# EducationalBoardV2F103RBT6.net
KiCad netlist of a schematic drawn in Altium Designer
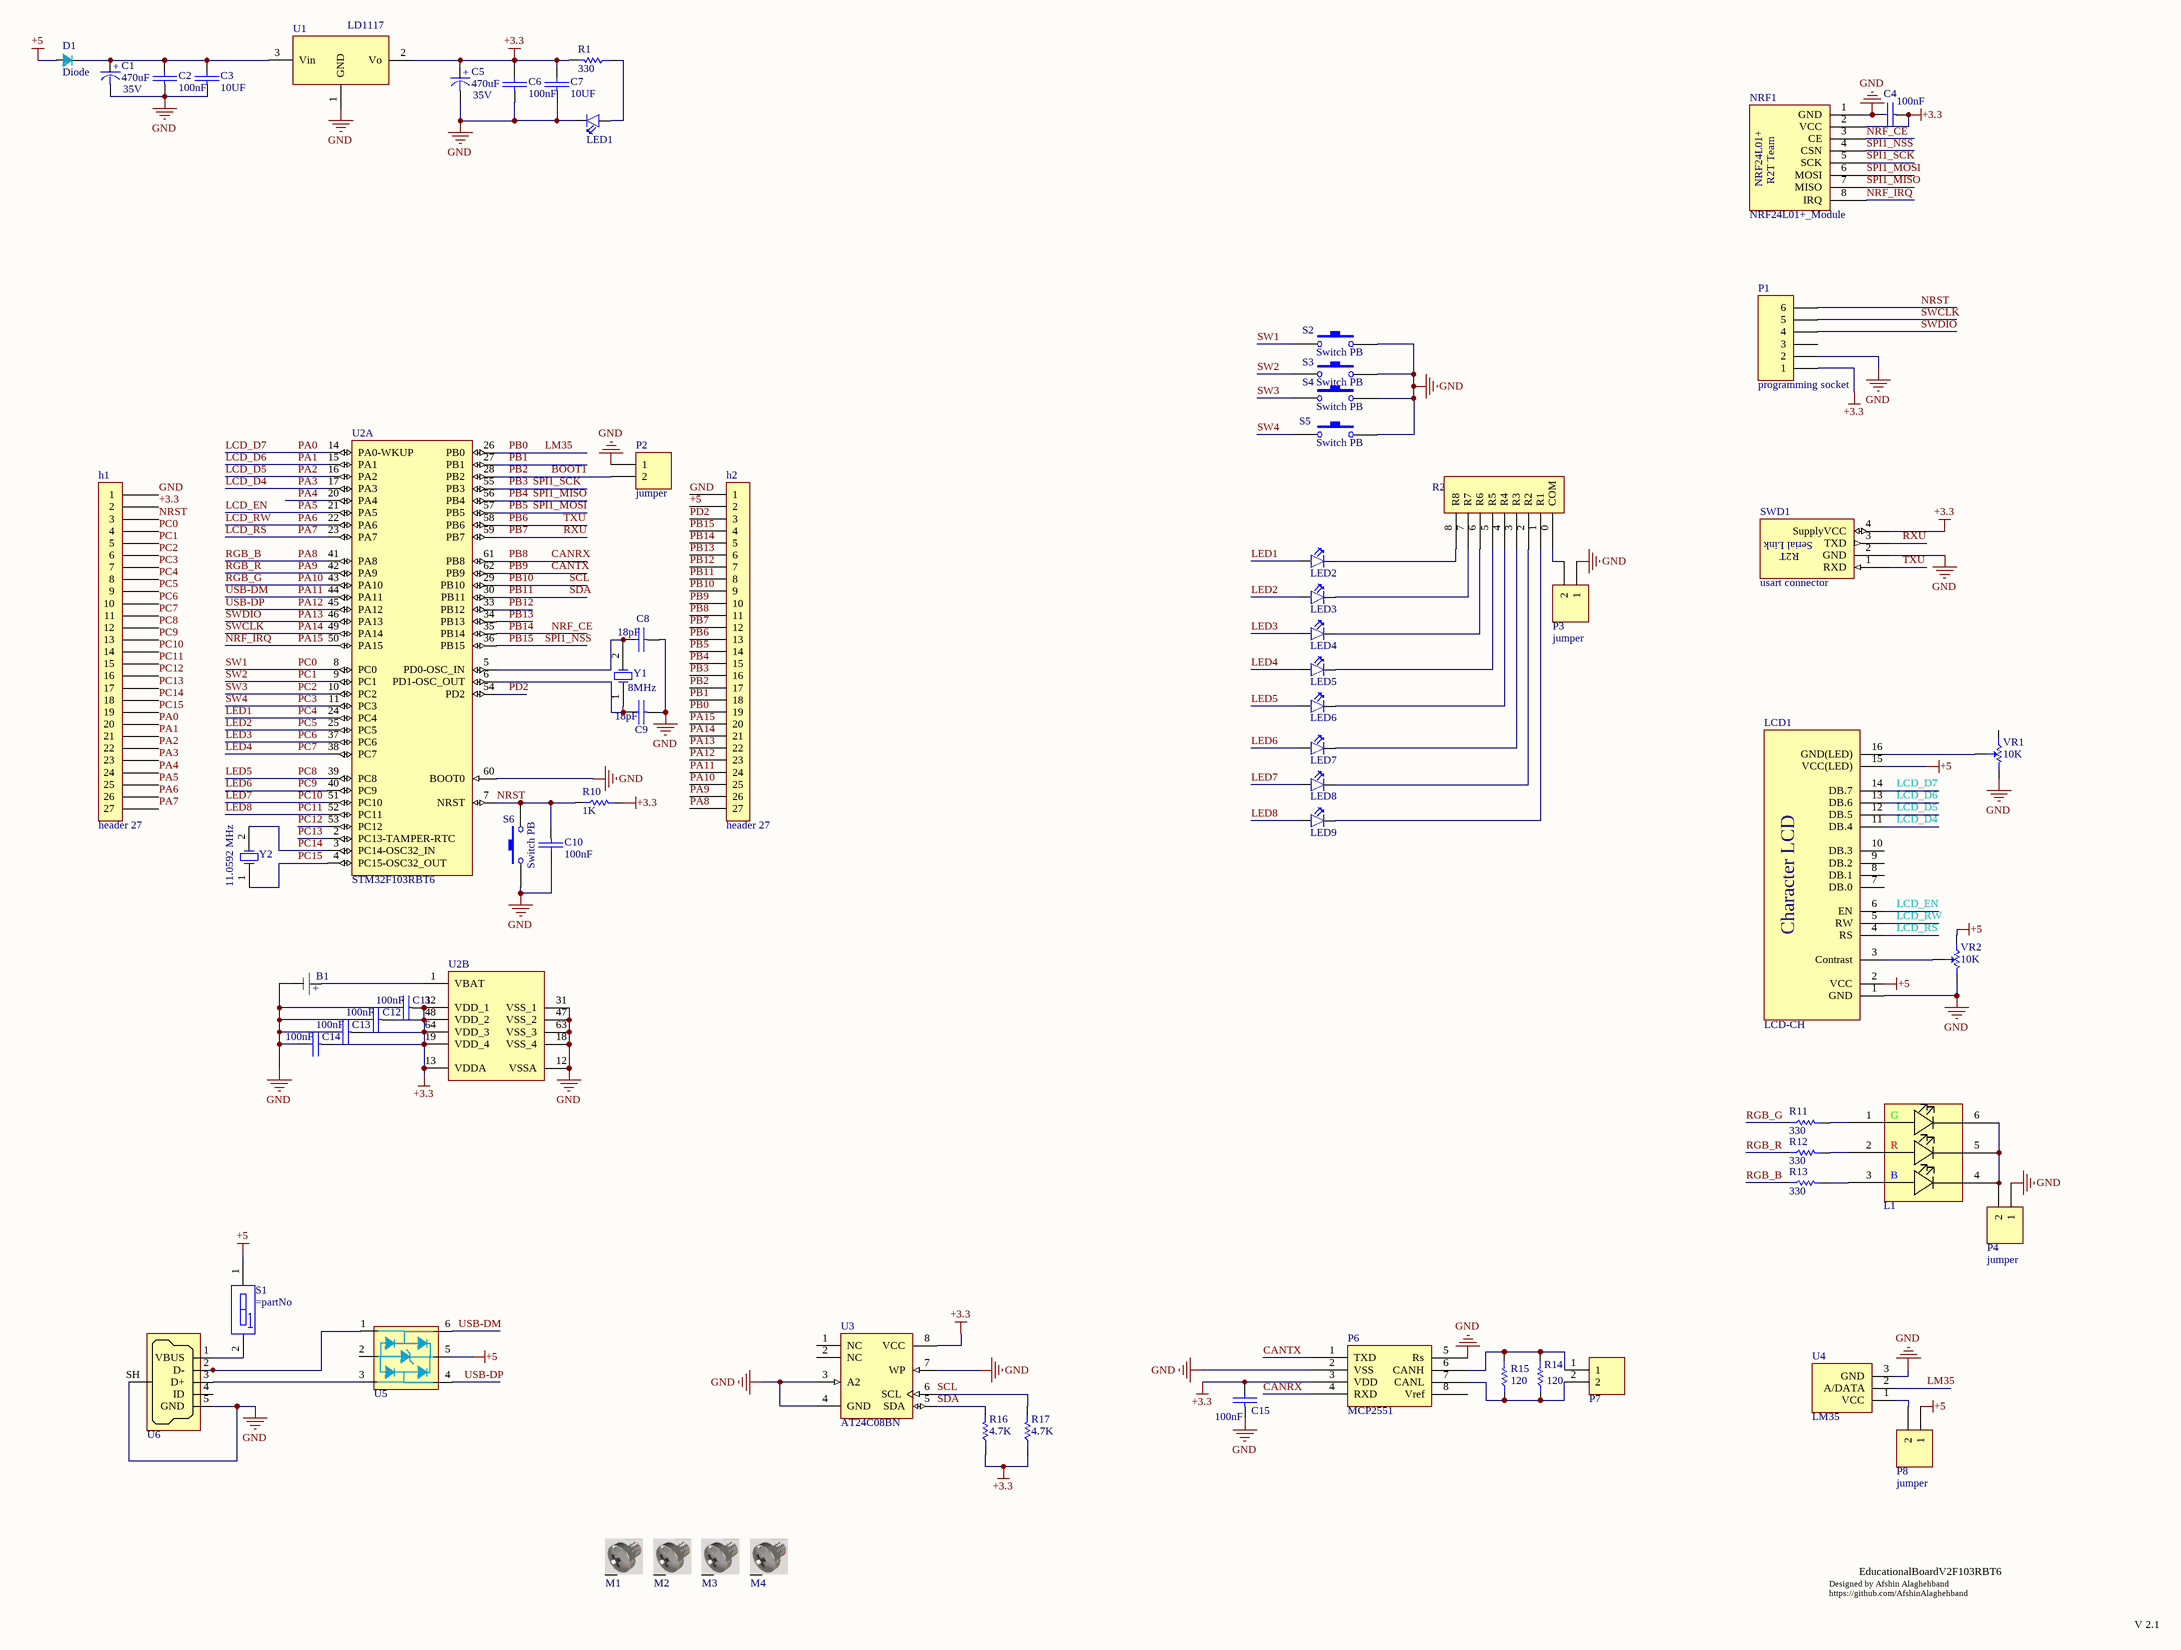
[diagram p0: EducationalBoardV2F103RBT6.SchDoc]

(export (version "E")
  (design (tool "Eeschema 10.0.6"))
  (components
    (comp (ref "B1")
      (value "BatteryHolder")
      (footprint "Battery Holder CR1220-SMD")
      (libsource (lib "R2T Team Library") (part "BatteryHolder"))
    )
    (comp (ref "C1")
      (value "470uF")
      (footprint "cap 03")
      (description "Polar Capacitor")
      (fields (field (name "VOLTAGE") "35V") (field (name "DESIGNER") "Saeid Jorablo"))
      (libsource (lib "My Library") (part "Cap-Polar"))
    )
    (comp (ref "C2")
      (value "100nF")
      (footprint "SMD_CAP_0805")
      (description "Bipolar Capacitor")
      (fields (field (name "VOLTAGE") "100V") (field (name "DESIGNER") "Saeid Jorablo"))
      (libsource (lib "My Library") (part "Cap-Bipolar"))
    )
    (comp (ref "C3")
      (value "10UF")
      (footprint "SMD_CAP_0805")
      (description "Bipolar Capacitor")
      (fields (field (name "VOLTAGE") "100V") (field (name "DESIGNER") "Saeid Jorablo"))
      (libsource (lib "My Library") (part "Cap-Bipolar"))
    )
    (comp (ref "C4")
      (value "100nF")
      (footprint "SMD_CAP_0805")
      (description "Bipolar Capacitor")
      (fields (field (name "VOLTAGE") "100V") (field (name "DESIGNER") "Saeid Jorablo"))
      (libsource (lib "My Library") (part "Cap-Bipolar"))
    )
    (comp (ref "C5")
      (value "470uF")
      (footprint "cap 03")
      (description "Polar Capacitor")
      (fields (field (name "VOLTAGE") "35V") (field (name "DESIGNER") "Saeid Jorablo"))
      (libsource (lib "My Library") (part "Cap-Polar"))
    )
    (comp (ref "C6")
      (value "100nF")
      (footprint "SMD_CAP_0805")
      (description "Bipolar Capacitor")
      (fields (field (name "VOLTAGE") "100V") (field (name "DESIGNER") "Saeid Jorablo"))
      (libsource (lib "My Library") (part "Cap-Bipolar"))
    )
    (comp (ref "C7")
      (value "10UF")
      (footprint "SMD_CAP_0805")
      (description "Bipolar Capacitor")
      (fields (field (name "VOLTAGE") "100V") (field (name "DESIGNER") "Saeid Jorablo"))
      (libsource (lib "My Library") (part "Cap-Bipolar"))
    )
    (comp (ref "C8")
      (value "18pF")
      (footprint "SMD_CAP_1206")
      (description "Bipolar Capacitor")
      (fields (field (name "VOLTAGE") "100V") (field (name "DESIGNER") "Saeid Jorablo"))
      (libsource (lib "My Library") (part "Cap-Bipolar"))
    )
    (comp (ref "C9")
      (value "18pF")
      (footprint "SMD_CAP_1206")
      (description "Bipolar Capacitor")
      (fields (field (name "VOLTAGE") "100V") (field (name "DESIGNER") "Saeid Jorablo"))
      (libsource (lib "My Library") (part "Cap-Bipolar"))
    )
    (comp (ref "C10")
      (value "100nF")
      (footprint "SMD_CAP_0805")
      (description "Bipolar Capacitor")
      (fields (field (name "VOLTAGE") "100V") (field (name "DESIGNER") "Saeid Jorablo"))
      (libsource (lib "My Library") (part "Cap-Bipolar"))
    )
    (comp (ref "C11")
      (value "100nF")
      (footprint "SMD_CAP_0805")
      (description "Bipolar Capacitor")
      (fields (field (name "VOLTAGE") "100V") (field (name "DESIGNER") "Saeid Jorablo"))
      (libsource (lib "My Library") (part "Cap-Bipolar"))
    )
    (comp (ref "C12")
      (value "100nF")
      (footprint "SMD_CAP_0805")
      (description "Bipolar Capacitor")
      (fields (field (name "VOLTAGE") "100V") (field (name "DESIGNER") "Saeid Jorablo"))
      (libsource (lib "My Library") (part "Cap-Bipolar"))
    )
    (comp (ref "C13")
      (value "100nF")
      (footprint "SMD_CAP_0805")
      (description "Bipolar Capacitor")
      (fields (field (name "VOLTAGE") "100V") (field (name "DESIGNER") "Saeid Jorablo"))
      (libsource (lib "My Library") (part "Cap-Bipolar"))
    )
    (comp (ref "C14")
      (value "100nF")
      (footprint "SMD_CAP_0805")
      (description "Bipolar Capacitor")
      (fields (field (name "VOLTAGE") "100V") (field (name "DESIGNER") "Saeid Jorablo"))
      (libsource (lib "My Library") (part "Cap-Bipolar"))
    )
    (comp (ref "C15")
      (value "100nF")
      (footprint "SMD_CAP_0805")
      (description "Bipolar Capacitor")
      (fields (field (name "VOLTAGE") "100V") (field (name "DESIGNER") "Saeid Jorablo"))
      (libsource (lib "My Library") (part "Cap-Bipolar"))
    )
    (comp (ref "D1")
      (value "Diodes")
      (footprint "DO-214AC ( SMD Diode )")
      (fields (field (name "DESCRIPTION:") "Diode") (field (name "DESIGNER :") "Hamed Jafarzadeh"))
      (libsource (lib "R2T Team Library") (part "Diodes"))
    )
    (comp (ref "h1")
      (value "header 27")
      (footprint "PCBComponent_1")
      (libsource (lib "my_lib_header27") (part "header 27"))
    )
    (comp (ref "h2")
      (value "header 27")
      (footprint "PCBComponent_1")
      (libsource (lib "") (part "header 27_1"))
    )
    (comp (ref "L1")
      (value "LED RGB")
      (footprint "LED_5050")
      (description "LED 5050 RGB")
      (libsource (lib "My_Lib_LED_RGB_5050") (part "LED RGB"))
    )
    (comp (ref "LCD1") (value "LCD-CH") (footprint "LCD2-16") (libsource (lib "My_lib_new") (part "LCD-CH")))
    (comp (ref "LED1")
      (value "LED")
      (footprint "LED0805")
      (fields (field (name "DESIGNER :") "Razi Research Team Of Mashhad - Hamed Jafarzadeh"))
      (libsource (lib "R2T Team Library") (part "LED"))
    )
    (comp (ref "LED2")
      (value "LED")
      (footprint "LED0805")
      (description "LED Red")
      (fields (field (name "DESIGNER :") "Razi Research Team Of Mashhad - Hamed Jafarzadeh"))
      (libsource (lib "R2T Team Library") (part "LED"))
    )
    (comp (ref "LED3")
      (value "LED")
      (footprint "LED0805")
      (description "LED Red")
      (fields (field (name "DESIGNER :") "Razi Research Team Of Mashhad - Hamed Jafarzadeh"))
      (libsource (lib "R2T Team Library") (part "LED"))
    )
    (comp (ref "LED4")
      (value "LED")
      (footprint "LED0805")
      (description "LED Red")
      (fields (field (name "DESIGNER :") "Razi Research Team Of Mashhad - Hamed Jafarzadeh"))
      (libsource (lib "R2T Team Library") (part "LED"))
    )
    (comp (ref "LED5")
      (value "LED")
      (footprint "LED0805")
      (description "LED Red")
      (fields (field (name "DESIGNER :") "Razi Research Team Of Mashhad - Hamed Jafarzadeh"))
      (libsource (lib "R2T Team Library") (part "LED"))
    )
    (comp (ref "LED6")
      (value "LED")
      (footprint "LED0805")
      (description "LED Red")
      (fields (field (name "DESIGNER :") "Razi Research Team Of Mashhad - Hamed Jafarzadeh"))
      (libsource (lib "R2T Team Library") (part "LED"))
    )
    (comp (ref "LED7")
      (value "LED")
      (footprint "LED0805")
      (description "LED Red")
      (fields (field (name "DESIGNER :") "Razi Research Team Of Mashhad - Hamed Jafarzadeh"))
      (libsource (lib "R2T Team Library") (part "LED"))
    )
    (comp (ref "LED8")
      (value "LED")
      (footprint "LED0805")
      (description "LED Red")
      (fields (field (name "DESIGNER :") "Razi Research Team Of Mashhad - Hamed Jafarzadeh"))
      (libsource (lib "R2T Team Library") (part "LED"))
    )
    (comp (ref "LED9")
      (value "LED")
      (footprint "LED0805")
      (description "LED Red")
      (fields (field (name "DESIGNER :") "Razi Research Team Of Mashhad - Hamed Jafarzadeh"))
      (libsource (lib "R2T Team Library") (part "LED"))
    )
    (comp (ref "M1")
      (value "Screw")
      (footprint "Board Screw_No Silk")
      (description "Board Screw With Spacer")
      (libsource (lib "My Library") (part "Board Screw"))
    )
    (comp (ref "M2")
      (value "Screw")
      (footprint "Board Screw_No Silk")
      (description "Board Screw With Spacer")
      (libsource (lib "My Library") (part "Board Screw"))
    )
    (comp (ref "M3")
      (value "Screw")
      (footprint "Board Screw_No Silk")
      (description "Board Screw With Spacer")
      (libsource (lib "My Library") (part "Board Screw"))
    )
    (comp (ref "M4")
      (value "Screw")
      (footprint "Board Screw_No Silk")
      (description "Board Screw With Spacer")
      (libsource (lib "My Library") (part "Board Screw"))
    )
    (comp (ref "NRF1")
      (value "NRF24L01+_Module")
      (footprint "NRF24L01+_Module")
      (fields (field (name "DESIGNER:") "HamedJafarzadeh"))
      (libsource (lib "R2T Team Library") (part "NRF24L01+_Module"))
    )
    (comp (ref "P1")
      (value "programming socket")
      (footprint "HDR1X6")
      (description "Header, 6-Pin")
      (fields (field (name "PUBLISHER") "Altium Limited"))
      (libsource (lib "Miscellaneous Connectors") (part "Header 6"))
    )
    (comp (ref "P2")
      (value "jumper")
      (footprint "HDR1X2")
      (description "Header, 2-Pin")
      (fields (field (name "PUBLISHER") "Altium Limited"))
      (libsource (lib "") (part "Header 2_1"))
    )
    (comp (ref "P3")
      (value "jumper")
      (footprint "HDR1X2")
      (description "Header, 2-Pin")
      (fields (field (name "PUBLISHER") "Altium Limited"))
      (libsource (lib "Miscellaneous Connectors") (part "Header 2"))
    )
    (comp (ref "P4")
      (value "jumper")
      (footprint "HDR1X2")
      (description "Header, 2-Pin")
      (fields (field (name "PUBLISHER") "Altium Limited"))
      (libsource (lib "Miscellaneous Connectors") (part "Header 2"))
    )
    (comp (ref "P6")
      (value "MCP2551")
      (footprint "MCP2551")
      (description "CAN TRANSCEIVERS")
      (libsource (lib "my_lib_MCP2552") (part "MCP2551"))
    )
    (comp (ref "P7")
      (value "can Connector")
      (footprint "PH Connector 2Pin")
      (fields (field (name "DESIGNER:") "Hamed Jafarzadeh - www.R2T.ir"))
      (libsource (lib "R2T Team Library") (part "Connector 2Pin"))
    )
    (comp (ref "P8")
      (value "jumper")
      (footprint "HDR1X2")
      (description "Header, 2-Pin")
      (fields (field (name "PUBLISHER") "Altium Limited"))
      (libsource (lib "Miscellaneous Connectors") (part "Header 2"))
    )
    (comp (ref "R1")
      (value "330")
      (footprint "RES 0805 (2012X06L)")
      (description "Resistor")
      (fields (field (name "TOLERANCE") "5%") (field (name "POWER") "1/8 W"))
      (libsource (lib "My Library") (part "Resistor"))
    )
    (comp (ref "R2")
      (value "ArrayResistor9pin")
      (footprint "ArrayRes9")
      (libsource (lib "My_Lib_ArrayResistor_9") (part "ArrayResistor9pin"))
    )
    (comp (ref "R10")
      (value "1K")
      (footprint "RES 0805 (2012X06L)")
      (description "Resistor")
      (fields (field (name "TOLERANCE") "5%") (field (name "POWER") "1/8 W"))
      (libsource (lib "My Library") (part "Resistor"))
    )
    (comp (ref "R11")
      (value "330")
      (footprint "RES 0805 (2012X06L)")
      (description "Resistor")
      (fields (field (name "TOLERANCE") "5%") (field (name "POWER") "1/8 W"))
      (libsource (lib "My Library") (part "Resistor"))
    )
    (comp (ref "R12")
      (value "330")
      (footprint "RES 0805 (2012X06L)")
      (description "Resistor")
      (fields (field (name "TOLERANCE") "5%") (field (name "POWER") "1/8 W"))
      (libsource (lib "My Library") (part "Resistor"))
    )
    (comp (ref "R13")
      (value "330")
      (footprint "RES 0805 (2012X06L)")
      (description "Resistor")
      (fields (field (name "TOLERANCE") "5%") (field (name "POWER") "1/8 W"))
      (libsource (lib "My Library") (part "Resistor"))
    )
    (comp (ref "R14")
      (value "120")
      (footprint "RES 0805 (2012X06L)")
      (description "Resistor")
      (libsource (lib "My Library") (part "Resistor"))
    )
    (comp (ref "R15")
      (value "120")
      (footprint "RES 0805 (2012X06L)")
      (description "Resistor")
      (fields (field (name "TOLERANCE") "5%") (field (name "POWER") "1/8 W"))
      (libsource (lib "My Library") (part "Resistor"))
    )
    (comp (ref "R16")
      (value "4.7K")
      (footprint "RES 0805 (2012X06L)")
      (description "Resistor")
      (fields (field (name "TOLERANCE") "5%") (field (name "POWER") "1/8 W"))
      (libsource (lib "My Library") (part "Resistor"))
    )
    (comp (ref "R17")
      (value "4.7K")
      (footprint "RES 0805 (2012X06L)")
      (description "Resistor")
      (fields (field (name "TOLERANCE") "5%") (field (name "POWER") "1/8 W"))
      (libsource (lib "My Library") (part "Resistor"))
    )
    (comp (ref "S1")
      (value "~")
      (footprint "418117170901")
      (description "WS-DITV 2.54 mm compact THT with flat actuator")
      (fields
        (field (name "MANUFACTURER") "Wurth Elektronik")
        (field (name "PART NO.") "418117170901")
        (field (name "CREATED BY") "Baojun Chen")
      )
      (libsource (lib "R2T Team Library") (part "DipSwitch1"))
    )
    (comp (ref "S2")
      (value "Switch PB")
      (footprint "SW-PB")
      (description "Push Button Switch")
      (libsource (lib "My Library") (part "Switch PB"))
    )
    (comp (ref "S3")
      (value "Switch PB")
      (footprint "SW-PB")
      (description "Push Button Switch")
      (libsource (lib "My Library") (part "Switch PB"))
    )
    (comp (ref "S4")
      (value "Switch PB")
      (footprint "SW-PB")
      (description "Push Button Switch")
      (libsource (lib "My Library") (part "Switch PB"))
    )
    (comp (ref "S5")
      (value "Switch PB")
      (footprint "SW-PB")
      (description "Push Button Switch")
      (libsource (lib "My Library") (part "Switch PB"))
    )
    (comp (ref "S6")
      (value "Switch PB")
      (footprint "SW-PB")
      (description "Push Button Switch")
      (libsource (lib "My Library") (part "Switch PB"))
    )
    (comp (ref "SWD1")
      (value "usart connector")
      (footprint "SerialWireMini")
      (libsource (lib "R2T Team Library") (part "R2T-MiniSerial"))
    )
    (comp (ref "U1") (value "LD1117") (footprint "TO-252-reg") (libsource (lib "AM_LIB") (part "LD1117")))
    (comp (ref "U2")
      (value "STM32F103RBT6")
      (footprint "STM-LQFP64_N")
      (description "ARM Cortex-M3 32-bit MCU")
      (fields (field (name "PARTNUMBER") "STM32F103RBT6"))
      (libsource (lib "ST Microelectronics STM32 F1") (part "STM32F103RBT6"))
    )
    (comp (ref "U3")
      (value "AT24C08BN")
      (footprint "8S1_N")
      (description "Serial EEPROM")
      (libsource (lib "Atmel Serial EEPROM") (part "AT24C08BN-SP25-B"))
    )
    (comp (ref "U4") (value "LM35") (footprint "LM35") (libsource (lib "My_lib_new") (part "LM35")))
    (comp (ref "U5")
      (value "USBLC6-2")
      (footprint "USBLC6-2")
      (description "Very low capacitance ESD protection;")
      (fields (field (name "DESIGNER") "Hamed Jafarzadeh"))
      (libsource (lib "R2T Team Library") (part "USBLC6-2"))
    )
    (comp (ref "U6")
      (value "USB OTG")
      (footprint "USB_Micro")
      (fields (field (name "DESIGNER:") "Hamed Jafarzadeh"))
      (libsource (lib "R2T Team Library") (part "USB OTG"))
    )
    (comp (ref "VR1")
      (value "10K")
      (footprint "Pot 00")
      (description "Variable Resistor")
      (fields (field (name "DESIGNER") "Saeid Jorablo"))
      (libsource (lib "My Library") (part "Resistor Variable"))
    )
    (comp (ref "VR2")
      (value "10K")
      (footprint "Pot 00")
      (description "Variable Resistor")
      (fields (field (name "DESIGNER") "Saeid Jorablo"))
      (libsource (lib "My Library") (part "Resistor Variable"))
    )
    (comp (ref "Y1")
      (value "8MHz")
      (footprint "XTAL Small")
      (description "XTAL Crystal")
      (libsource (lib "My Library") (part "XTAL"))
    )
    (comp (ref "Y2")
      (value "11.0592 MHz")
      (footprint "XTAL RTC")
      (description "XTAL Crystal")
      (libsource (lib "My Library") (part "XTAL"))
    )
  )
  (nets
    (net (code "1") (name "+3.3") (class "Default")
      (node (ref "C11") (pin "2") (pinfunction "-_2") (pintype "passive"))
      (node (ref "C12") (pin "2") (pinfunction "-_2") (pintype "passive"))
      (node (ref "C13") (pin "2") (pinfunction "-_2") (pintype "passive"))
      (node (ref "C14") (pin "2") (pinfunction "-_2") (pintype "passive"))
      (node (ref "C15") (pin "1") (pinfunction "+_1") (pintype "passive"))
      (node (ref "C4") (pin "2") (pinfunction "-_2") (pintype "passive"))
      (node (ref "C5") (pin "1") (pinfunction "+_1") (pintype "passive"))
      (node (ref "C6") (pin "1") (pinfunction "+_1") (pintype "passive"))
      (node (ref "C7") (pin "1") (pinfunction "+_1") (pintype "passive"))
      (node (ref "NRF1") (pin "2") (pinfunction "VCC_2") (pintype "passive"))
      (node (ref "P1") (pin "1") (pinfunction "1_1") (pintype "passive"))
      (node (ref "P6") (pin "3") (pinfunction "VDD_3") (pintype "passive"))
      (node (ref "R1") (pin "2") (pinfunction "2_2") (pintype "passive"))
      (node (ref "R10") (pin "2") (pinfunction "2_2") (pintype "passive"))
      (node (ref "R16") (pin "1") (pinfunction "1_1") (pintype "passive"))
      (node (ref "R17") (pin "1") (pinfunction "1_1") (pintype "passive"))
      (node (ref "SWD1") (pin "4") (pinfunction "SupplyVCC_4") (pintype "bidirectional"))
      (node (ref "U1") (pin "2") (pinfunction "Vo_2") (pintype "passive"))
      (node (ref "U2") (pin "13") (pinfunction "VDDA_13") (pintype "power_in"))
      (node (ref "U2") (pin "19") (pinfunction "VDD_4_19") (pintype "power_in"))
      (node (ref "U2") (pin "32") (pinfunction "VDD_1_32") (pintype "power_in"))
      (node (ref "U2") (pin "48") (pinfunction "VDD_2_48") (pintype "power_in"))
      (node (ref "U2") (pin "64") (pinfunction "VDD_3_64") (pintype "power_in"))
      (node (ref "U3") (pin "8") (pinfunction "VCC_8") (pintype "power_in"))
      (node (ref "h1") (pin "2") (pinfunction "2_2") (pintype "passive"))
    )
    (net (code "2") (name "+5") (class "Default")
      (node (ref "D1") (pin "0") (pintype "passive"))
      (node (ref "LCD1") (pin "15") (pinfunction "VCC(LED)_15") (pintype "passive"))
      (node (ref "LCD1") (pin "2") (pinfunction "VCC_2") (pintype "passive"))
      (node (ref "P8") (pin "1") (pinfunction "1_1") (pintype "passive"))
      (node (ref "S1") (pin "1") (pinfunction "1_1") (pintype "passive"))
      (node (ref "U5") (pin "5") (pinfunction "0_5") (pintype "passive"))
      (node (ref "VR2") (pin "1") (pinfunction "CCW_1") (pintype "passive"))
      (node (ref "h2") (pin "2") (pinfunction "2_2") (pintype "passive"))
    )
    (net (code "3") (name "/BOOT1") (class "Default")
      (node (ref "P2") (pin "2") (pinfunction "2_2") (pintype "passive"))
      (node (ref "U2") (pin "28") (pinfunction "PB2_28") (pintype "bidirectional"))
      (node (ref "h2") (pin "17") (pinfunction "17_17") (pintype "passive"))
    )
    (net (code "4") (name "/CANRX") (class "Default")
      (node (ref "P6") (pin "4") (pinfunction "RXD_4") (pintype "passive"))
      (node (ref "U2") (pin "61") (pinfunction "PB8_61") (pintype "bidirectional"))
      (node (ref "h2") (pin "11") (pinfunction "11_11") (pintype "passive"))
    )
    (net (code "5") (name "/CANTX") (class "Default")
      (node (ref "P6") (pin "1") (pinfunction "TXD_1") (pintype "passive"))
      (node (ref "U2") (pin "62") (pinfunction "PB9_62") (pintype "bidirectional"))
      (node (ref "h2") (pin "10") (pinfunction "10_10") (pintype "passive"))
    )
    (net (code "6") (name "/LCD_D4") (class "Default")
      (node (ref "LCD1") (pin "11") (pinfunction "DB.4_11") (pintype "passive"))
      (node (ref "U2") (pin "17") (pinfunction "PA3_17") (pintype "bidirectional"))
      (node (ref "h1") (pin "23") (pinfunction "23_23") (pintype "passive"))
    )
    (net (code "7") (name "/LCD_D5") (class "Default")
      (node (ref "LCD1") (pin "12") (pinfunction "DB.5_12") (pintype "passive"))
      (node (ref "U2") (pin "16") (pinfunction "PA2_16") (pintype "bidirectional"))
      (node (ref "h1") (pin "22") (pinfunction "22_22") (pintype "passive"))
    )
    (net (code "8") (name "/LCD_D6") (class "Default")
      (node (ref "LCD1") (pin "13") (pinfunction "DB.6_13") (pintype "passive"))
      (node (ref "U2") (pin "15") (pinfunction "PA1_15") (pintype "bidirectional"))
      (node (ref "h1") (pin "21") (pinfunction "21_21") (pintype "passive"))
    )
    (net (code "9") (name "/LCD_D7") (class "Default")
      (node (ref "LCD1") (pin "14") (pinfunction "DB.7_14") (pintype "passive"))
      (node (ref "U2") (pin "14") (pinfunction "PA0-WKUP_14") (pintype "bidirectional"))
      (node (ref "h1") (pin "20") (pinfunction "20_20") (pintype "passive"))
    )
    (net (code "10") (name "/LCD_EN") (class "Default")
      (node (ref "LCD1") (pin "6") (pinfunction "EN_6") (pintype "passive"))
      (node (ref "U2") (pin "21") (pinfunction "PA5_21") (pintype "bidirectional"))
      (node (ref "h1") (pin "25") (pinfunction "25_25") (pintype "passive"))
    )
    (net (code "11") (name "/LCD_RS") (class "Default")
      (node (ref "LCD1") (pin "4") (pinfunction "RS_4") (pintype "passive"))
      (node (ref "U2") (pin "23") (pinfunction "PA7_23") (pintype "bidirectional"))
      (node (ref "h1") (pin "27") (pinfunction "27_27") (pintype "passive"))
    )
    (net (code "12") (name "/LCD_RW") (class "Default")
      (node (ref "LCD1") (pin "5") (pinfunction "RW_5") (pintype "passive"))
      (node (ref "U2") (pin "22") (pinfunction "PA6_22") (pintype "bidirectional"))
      (node (ref "h1") (pin "26") (pinfunction "26_26") (pintype "passive"))
    )
    (net (code "13") (name "/LED1") (class "Default")
      (node (ref "LED2") (pin "1") (pinfunction "A_1") (pintype "passive"))
      (node (ref "U2") (pin "24") (pinfunction "PC4_24") (pintype "bidirectional"))
      (node (ref "h1") (pin "8") (pinfunction "8_8") (pintype "passive"))
    )
    (net (code "14") (name "/LED2") (class "Default")
      (node (ref "LED3") (pin "1") (pinfunction "A_1") (pintype "passive"))
      (node (ref "U2") (pin "25") (pinfunction "PC5_25") (pintype "bidirectional"))
      (node (ref "h1") (pin "9") (pinfunction "9_9") (pintype "passive"))
    )
    (net (code "15") (name "/LED3") (class "Default")
      (node (ref "LED4") (pin "1") (pinfunction "A_1") (pintype "passive"))
      (node (ref "U2") (pin "37") (pinfunction "PC6_37") (pintype "bidirectional"))
      (node (ref "h1") (pin "10") (pinfunction "10_10") (pintype "passive"))
    )
    (net (code "16") (name "/LED4") (class "Default")
      (node (ref "LED5") (pin "1") (pinfunction "A_1") (pintype "passive"))
      (node (ref "U2") (pin "38") (pinfunction "PC7_38") (pintype "bidirectional"))
      (node (ref "h1") (pin "11") (pinfunction "11_11") (pintype "passive"))
    )
    (net (code "17") (name "/LED5") (class "Default")
      (node (ref "LED6") (pin "1") (pinfunction "A_1") (pintype "passive"))
      (node (ref "U2") (pin "39") (pinfunction "PC8_39") (pintype "bidirectional"))
      (node (ref "h1") (pin "12") (pinfunction "12_12") (pintype "passive"))
    )
    (net (code "18") (name "/LED6") (class "Default")
      (node (ref "LED7") (pin "1") (pinfunction "A_1") (pintype "passive"))
      (node (ref "U2") (pin "40") (pinfunction "PC9_40") (pintype "bidirectional"))
      (node (ref "h1") (pin "13") (pinfunction "13_13") (pintype "passive"))
    )
    (net (code "19") (name "/LED7") (class "Default")
      (node (ref "LED8") (pin "1") (pinfunction "A_1") (pintype "passive"))
      (node (ref "U2") (pin "51") (pinfunction "PC10_51") (pintype "bidirectional"))
      (node (ref "h1") (pin "14") (pinfunction "14_14") (pintype "passive"))
    )
    (net (code "20") (name "/LED8") (class "Default")
      (node (ref "LED9") (pin "1") (pinfunction "A_1") (pintype "passive"))
      (node (ref "U2") (pin "52") (pinfunction "PC11_52") (pintype "bidirectional"))
      (node (ref "h1") (pin "15") (pinfunction "15_15") (pintype "passive"))
    )
    (net (code "21") (name "/LM35") (class "Default")
      (node (ref "U2") (pin "26") (pinfunction "PB0_26") (pintype "bidirectional"))
      (node (ref "U4") (pin "2") (pinfunction "A/DATA_2") (pintype "passive"))
      (node (ref "h2") (pin "19") (pinfunction "19_19") (pintype "passive"))
    )
    (net (code "22") (name "/NRF_CE") (class "Default")
      (node (ref "NRF1") (pin "3") (pinfunction "CE_3") (pintype "passive"))
      (node (ref "U2") (pin "35") (pinfunction "PB14_35") (pintype "bidirectional"))
      (node (ref "h2") (pin "5") (pinfunction "5_5") (pintype "passive"))
    )
    (net (code "23") (name "/NRF_IRQ") (class "Default")
      (node (ref "NRF1") (pin "8") (pinfunction "IRQ_8") (pintype "passive"))
      (node (ref "U2") (pin "50") (pinfunction "PA15_50") (pintype "bidirectional"))
      (node (ref "h2") (pin "20") (pinfunction "20_20") (pintype "passive"))
    )
    (net (code "24") (name "/NRST") (class "Default")
      (node (ref "C10") (pin "2") (pinfunction "-_2") (pintype "passive"))
      (node (ref "P1") (pin "6") (pinfunction "6_6") (pintype "passive"))
      (node (ref "R10") (pin "1") (pinfunction "1_1") (pintype "passive"))
      (node (ref "S6") (pin "2") (pinfunction "2_2") (pintype "passive"))
      (node (ref "U2") (pin "7") (pinfunction "NRST_7") (pintype "bidirectional"))
      (node (ref "h1") (pin "3") (pinfunction "3_3") (pintype "passive"))
    )
    (net (code "25") (name "/PA4") (class "Default")
      (node (ref "U2") (pin "20") (pinfunction "PA4_20") (pintype "bidirectional"))
      (node (ref "h1") (pin "24") (pinfunction "24_24") (pintype "passive"))
    )
    (net (code "26") (name "/PA8") (class "Default")
      (node (ref "R13") (pin "1") (pinfunction "1_1") (pintype "passive"))
      (node (ref "U2") (pin "41") (pinfunction "PA8_41") (pintype "bidirectional"))
      (node (ref "h2") (pin "27") (pinfunction "27_27") (pintype "passive"))
    )
    (net (code "27") (name "/PA9") (class "Default")
      (node (ref "R12") (pin "1") (pinfunction "1_1") (pintype "passive"))
      (node (ref "U2") (pin "42") (pinfunction "PA9_42") (pintype "bidirectional"))
      (node (ref "h2") (pin "26") (pinfunction "26_26") (pintype "passive"))
    )
    (net (code "28") (name "/PA10") (class "Default")
      (node (ref "R11") (pin "1") (pinfunction "1_1") (pintype "passive"))
      (node (ref "U2") (pin "43") (pinfunction "PA10_43") (pintype "bidirectional"))
      (node (ref "h2") (pin "25") (pinfunction "25_25") (pintype "passive"))
    )
    (net (code "29") (name "/PA11") (class "Default")
      (node (ref "U2") (pin "44") (pinfunction "PA11_44") (pintype "bidirectional"))
      (node (ref "U5") (pin "6") (pinfunction "IO_6") (pintype "passive"))
      (node (ref "h2") (pin "24") (pinfunction "24_24") (pintype "passive"))
    )
    (net (code "30") (name "/PA12") (class "Default")
      (node (ref "U2") (pin "45") (pinfunction "PA12_45") (pintype "bidirectional"))
      (node (ref "U5") (pin "4") (pinfunction "0_4") (pintype "passive"))
      (node (ref "h2") (pin "23") (pinfunction "23_23") (pintype "passive"))
    )
    (net (code "31") (name "/PA13") (class "Default")
      (node (ref "P1") (pin "4") (pinfunction "4_4") (pintype "passive"))
      (node (ref "U2") (pin "46") (pinfunction "PA13_46") (pintype "bidirectional"))
      (node (ref "h2") (pin "22") (pinfunction "22_22") (pintype "passive"))
    )
    (net (code "32") (name "/PA14") (class "Default")
      (node (ref "P1") (pin "5") (pinfunction "5_5") (pintype "passive"))
      (node (ref "U2") (pin "49") (pinfunction "PA14_49") (pintype "bidirectional"))
      (node (ref "h2") (pin "21") (pinfunction "21_21") (pintype "passive"))
    )
    (net (code "33") (name "/PB1") (class "Default")
      (node (ref "U2") (pin "27") (pinfunction "PB1_27") (pintype "bidirectional"))
      (node (ref "h2") (pin "18") (pinfunction "18_18") (pintype "passive"))
    )
    (net (code "34") (name "/PB3") (class "Default")
      (node (ref "NRF1") (pin "5") (pinfunction "SCK_5") (pintype "passive"))
      (node (ref "U2") (pin "55") (pinfunction "PB3_55") (pintype "bidirectional"))
      (node (ref "h2") (pin "16") (pinfunction "16_16") (pintype "passive"))
    )
    (net (code "35") (name "/PB4") (class "Default")
      (node (ref "NRF1") (pin "7") (pinfunction "MISO_7") (pintype "passive"))
      (node (ref "U2") (pin "56") (pinfunction "PB4_56") (pintype "bidirectional"))
      (node (ref "h2") (pin "15") (pinfunction "15_15") (pintype "passive"))
    )
    (net (code "36") (name "/PB5") (class "Default")
      (node (ref "NRF1") (pin "6") (pinfunction "MOSI_6") (pintype "passive"))
      (node (ref "U2") (pin "57") (pinfunction "PB5_57") (pintype "bidirectional"))
      (node (ref "h2") (pin "14") (pinfunction "14_14") (pintype "passive"))
    )
    (net (code "37") (name "/PB6") (class "Default")
      (node (ref "SWD1") (pin "1") (pinfunction "RXD_1") (pintype "input"))
      (node (ref "U2") (pin "58") (pinfunction "PB6_58") (pintype "bidirectional"))
      (node (ref "h2") (pin "13") (pinfunction "13_13") (pintype "passive"))
    )
    (net (code "38") (name "/PB7") (class "Default")
      (node (ref "SWD1") (pin "3") (pinfunction "TXD_3") (pintype "output"))
      (node (ref "U2") (pin "59") (pinfunction "PB7_59") (pintype "bidirectional"))
      (node (ref "h2") (pin "12") (pinfunction "12_12") (pintype "passive"))
    )
    (net (code "39") (name "/PB10") (class "Default")
      (node (ref "R17") (pin "2") (pinfunction "2_2") (pintype "passive"))
      (node (ref "U2") (pin "29") (pinfunction "PB10_29") (pintype "bidirectional"))
      (node (ref "U3") (pin "6") (pinfunction "SCL_6") (pintype "input"))
      (node (ref "h2") (pin "9") (pinfunction "9_9") (pintype "passive"))
    )
    (net (code "40") (name "/PB11") (class "Default")
      (node (ref "R16") (pin "2") (pinfunction "2_2") (pintype "passive"))
      (node (ref "U2") (pin "30") (pinfunction "PB11_30") (pintype "bidirectional"))
      (node (ref "U3") (pin "5") (pinfunction "SDA_5") (pintype "bidirectional"))
      (node (ref "h2") (pin "8") (pinfunction "8_8") (pintype "passive"))
    )
    (net (code "41") (name "/PB12") (class "Default")
      (node (ref "U2") (pin "33") (pinfunction "PB12_33") (pintype "bidirectional"))
      (node (ref "h2") (pin "7") (pinfunction "7_7") (pintype "passive"))
    )
    (net (code "42") (name "/PB13") (class "Default")
      (node (ref "U2") (pin "34") (pinfunction "PB13_34") (pintype "bidirectional"))
      (node (ref "h2") (pin "6") (pinfunction "6_6") (pintype "passive"))
    )
    (net (code "43") (name "/PB15") (class "Default")
      (node (ref "NRF1") (pin "4") (pinfunction "CSN_4") (pintype "passive"))
      (node (ref "U2") (pin "36") (pinfunction "PB15_36") (pintype "bidirectional"))
      (node (ref "h2") (pin "4") (pinfunction "4_4") (pintype "passive"))
    )
    (net (code "44") (name "/PC0") (class "Default")
      (node (ref "S2") (pin "1") (pinfunction "1_1") (pintype "passive"))
      (node (ref "U2") (pin "8") (pinfunction "PC0_8") (pintype "bidirectional"))
      (node (ref "h1") (pin "4") (pinfunction "4_4") (pintype "passive"))
    )
    (net (code "45") (name "/PC1") (class "Default")
      (node (ref "S3") (pin "1") (pinfunction "1_1") (pintype "passive"))
      (node (ref "U2") (pin "9") (pinfunction "PC1_9") (pintype "bidirectional"))
      (node (ref "h1") (pin "5") (pinfunction "5_5") (pintype "passive"))
    )
    (net (code "46") (name "/PC2") (class "Default")
      (node (ref "S4") (pin "1") (pinfunction "1_1") (pintype "passive"))
      (node (ref "U2") (pin "10") (pinfunction "PC2_10") (pintype "bidirectional"))
      (node (ref "h1") (pin "6") (pinfunction "6_6") (pintype "passive"))
    )
    (net (code "47") (name "/PC3") (class "Default")
      (node (ref "S5") (pin "1") (pinfunction "1_1") (pintype "passive"))
      (node (ref "U2") (pin "11") (pinfunction "PC3_11") (pintype "bidirectional"))
      (node (ref "h1") (pin "7") (pinfunction "7_7") (pintype "passive"))
    )
    (net (code "48") (name "/PC12") (class "Default")
      (node (ref "U2") (pin "53") (pinfunction "PC12_53") (pintype "bidirectional"))
      (node (ref "h1") (pin "16") (pinfunction "16_16") (pintype "passive"))
    )
    (net (code "49") (name "/PC13") (class "Default")
      (node (ref "U2") (pin "2") (pinfunction "PC13-TAMPER-RTC_2") (pintype "bidirectional"))
      (node (ref "h1") (pin "17") (pinfunction "17_17") (pintype "passive"))
    )
    (net (code "50") (name "/PC14") (class "Default")
      (node (ref "U2") (pin "3") (pinfunction "PC14-OSC32_IN_3") (pintype "bidirectional"))
      (node (ref "Y2") (pin "2") (pinfunction "OSC2_2") (pintype "passive"))
      (node (ref "h1") (pin "18") (pinfunction "18_18") (pintype "passive"))
    )
    (net (code "51") (name "/PC15") (class "Default")
      (node (ref "U2") (pin "4") (pinfunction "PC15-OSC32_OUT_4") (pintype "bidirectional"))
      (node (ref "Y2") (pin "1") (pinfunction "OSC1_1") (pintype "passive"))
      (node (ref "h1") (pin "19") (pinfunction "19_19") (pintype "passive"))
    )
    (net (code "52") (name "/PD2") (class "Default")
      (node (ref "U2") (pin "54") (pinfunction "PD2_54") (pintype "bidirectional"))
      (node (ref "h2") (pin "3") (pinfunction "3_3") (pintype "passive"))
    )
    (net (code "53") (name "GND") (class "Default")
      (node (ref "B1") (pin "2") (pintype "passive"))
      (node (ref "C1") (pin "2") (pinfunction "-_2") (pintype "passive"))
      (node (ref "C10") (pin "1") (pinfunction "+_1") (pintype "passive"))
      (node (ref "C11") (pin "1") (pinfunction "+_1") (pintype "passive"))
      (node (ref "C12") (pin "1") (pinfunction "+_1") (pintype "passive"))
      (node (ref "C13") (pin "1") (pinfunction "+_1") (pintype "passive"))
      (node (ref "C14") (pin "1") (pinfunction "+_1") (pintype "passive"))
      (node (ref "C15") (pin "2") (pinfunction "-_2") (pintype "passive"))
      (node (ref "C2") (pin "2") (pinfunction "-_2") (pintype "passive"))
      (node (ref "C3") (pin "2") (pinfunction "-_2") (pintype "passive"))
      (node (ref "C4") (pin "1") (pinfunction "+_1") (pintype "passive"))
      (node (ref "C5") (pin "2") (pinfunction "-_2") (pintype "passive"))
      (node (ref "C6") (pin "2") (pinfunction "-_2") (pintype "passive"))
      (node (ref "C7") (pin "2") (pinfunction "-_2") (pintype "passive"))
      (node (ref "C8") (pin "2") (pinfunction "-_2") (pintype "passive"))
      (node (ref "C9") (pin "2") (pinfunction "-_2") (pintype "passive"))
      (node (ref "LCD1") (pin "1") (pinfunction "GND_1") (pintype "passive"))
      (node (ref "LED1") (pin "2") (pinfunction "K_2") (pintype "passive"))
      (node (ref "NRF1") (pin "1") (pinfunction "GND_1") (pintype "passive"))
      (node (ref "P1") (pin "2") (pinfunction "2_2") (pintype "passive"))
      (node (ref "P2") (pin "1") (pinfunction "1_1") (pintype "passive"))
      (node (ref "P3") (pin "1") (pinfunction "1_1") (pintype "passive"))
      (node (ref "P4") (pin "1") (pinfunction "1_1") (pintype "passive"))
      (node (ref "P6") (pin "2") (pinfunction "VSS_2") (pintype "passive"))
      (node (ref "P6") (pin "5") (pinfunction "Rs_5") (pintype "passive"))
      (node (ref "S2") (pin "2") (pinfunction "2_2") (pintype "passive"))
      (node (ref "S3") (pin "2") (pinfunction "2_2") (pintype "passive"))
      (node (ref "S4") (pin "2") (pinfunction "2_2") (pintype "passive"))
      (node (ref "S5") (pin "2") (pinfunction "2_2") (pintype "passive"))
      (node (ref "S6") (pin "1") (pinfunction "1_1") (pintype "passive"))
      (node (ref "SWD1") (pin "2") (pinfunction "GND_2") (pintype "passive"))
      (node (ref "U1") (pin "1") (pinfunction "GND_1") (pintype "passive"))
      (node (ref "U2") (pin "12") (pinfunction "VSSA_12") (pintype "power_in"))
      (node (ref "U2") (pin "18") (pinfunction "VSS_4_18") (pintype "power_in"))
      (node (ref "U2") (pin "31") (pinfunction "VSS_1_31") (pintype "power_in"))
      (node (ref "U2") (pin "47") (pinfunction "VSS_2_47") (pintype "power_in"))
      (node (ref "U2") (pin "60") (pinfunction "BOOT0_60") (pintype "input"))
      (node (ref "U2") (pin "63") (pinfunction "VSS_3_63") (pintype "power_in"))
      (node (ref "U3") (pin "3") (pinfunction "A2_3") (pintype "input"))
      (node (ref "U3") (pin "4") (pinfunction "GND_4") (pintype "power_in"))
      (node (ref "U3") (pin "7") (pinfunction "WP_7") (pintype "input"))
      (node (ref "U4") (pin "3") (pinfunction "GND_3") (pintype "passive"))
      (node (ref "U6") (pin "5") (pinfunction "GND_5") (pintype "passive"))
      (node (ref "U6") (pin "SH") (pinfunction "Shell_SH") (pintype "passive"))
      (node (ref "VR1") (pin "2") (pinfunction "CW_2") (pintype "passive"))
      (node (ref "VR2") (pin "2") (pinfunction "CW_2") (pintype "passive"))
      (node (ref "h1") (pin "1") (pinfunction "1_1") (pintype "passive"))
      (node (ref "h2") (pin "1") (pinfunction "1_1") (pintype "passive"))
    )
    (net (code "54") (name "Net-(C1-+)") (class "Default")
      (node (ref "C1") (pin "1") (pinfunction "+_1") (pintype "passive"))
      (node (ref "C2") (pin "1") (pinfunction "+_1") (pintype "passive"))
      (node (ref "C3") (pin "1") (pinfunction "+_1") (pintype "passive"))
      (node (ref "D1") (pin "1") (pintype "passive"))
      (node (ref "U1") (pin "3") (pinfunction "Vin_3") (pintype "passive"))
    )
    (net (code "55") (name "Net-(C8-+)") (class "Default")
      (node (ref "C8") (pin "1") (pinfunction "+_1") (pintype "passive"))
      (node (ref "U2") (pin "5") (pinfunction "PD0-OSC_IN_5") (pintype "bidirectional"))
      (node (ref "Y1") (pin "2") (pinfunction "OSC2_2") (pintype "passive"))
    )
    (net (code "56") (name "Net-(C9-+)") (class "Default")
      (node (ref "C9") (pin "1") (pinfunction "+_1") (pintype "passive"))
      (node (ref "U2") (pin "6") (pinfunction "PD1-OSC_OUT_6") (pintype "bidirectional"))
      (node (ref "Y1") (pin "1") (pinfunction "OSC1_1") (pintype "passive"))
    )
    (net (code "57") (name "Net-(L1-B)") (class "Default")
      (node (ref "L1") (pin "3") (pinfunction "B_3") (pintype "tri_state"))
      (node (ref "R13") (pin "2") (pinfunction "2_2") (pintype "passive"))
    )
    (net (code "58") (name "Net-(L1-G)") (class "Default")
      (node (ref "L1") (pin "1") (pinfunction "G_1") (pintype "tri_state"))
      (node (ref "R11") (pin "2") (pinfunction "2_2") (pintype "passive"))
    )
    (net (code "59") (name "Net-(L1-Pad4)") (class "Default")
      (node (ref "L1") (pin "4") (pinfunction "4_4") (pintype "tri_state"))
      (node (ref "L1") (pin "5") (pinfunction "5_5") (pintype "tri_state"))
      (node (ref "L1") (pin "6") (pinfunction "6_6") (pintype "tri_state"))
      (node (ref "P4") (pin "2") (pinfunction "2_2") (pintype "passive"))
    )
    (net (code "60") (name "Net-(L1-R)") (class "Default")
      (node (ref "L1") (pin "2") (pinfunction "R_2") (pintype "tri_state"))
      (node (ref "R12") (pin "2") (pinfunction "2_2") (pintype "passive"))
    )
    (net (code "61") (name "Net-(LCD1-Contrast)") (class "Default")
      (node (ref "LCD1") (pin "3") (pinfunction "Contrast_3") (pintype "passive"))
      (node (ref "VR2") (pin "3") (pinfunction "Setpoint_3") (pintype "passive"))
    )
    (net (code "62") (name "Net-(LCD1-GND(LED))") (class "Default")
      (node (ref "LCD1") (pin "16") (pinfunction "GND(LED)_16") (pintype "passive"))
      (node (ref "VR1") (pin "3") (pinfunction "Setpoint_3") (pintype "passive"))
    )
    (net (code "63") (name "Net-(LED1-A)") (class "Default")
      (node (ref "LED1") (pin "1") (pinfunction "A_1") (pintype "passive"))
      (node (ref "R1") (pin "1") (pinfunction "1_1") (pintype "passive"))
    )
    (net (code "64") (name "Net-(LED2-K)") (class "Default")
      (node (ref "LED2") (pin "2") (pinfunction "K_2") (pintype "passive"))
      (node (ref "R2") (pin "8") (pinfunction "R8_8") (pintype "passive"))
    )
    (net (code "65") (name "Net-(LED3-K)") (class "Default")
      (node (ref "LED3") (pin "2") (pinfunction "K_2") (pintype "passive"))
      (node (ref "R2") (pin "7") (pinfunction "R7_7") (pintype "passive"))
    )
    (net (code "66") (name "Net-(LED4-K)") (class "Default")
      (node (ref "LED4") (pin "2") (pinfunction "K_2") (pintype "passive"))
      (node (ref "R2") (pin "6") (pinfunction "R6_6") (pintype "passive"))
    )
    (net (code "67") (name "Net-(LED5-K)") (class "Default")
      (node (ref "LED5") (pin "2") (pinfunction "K_2") (pintype "passive"))
      (node (ref "R2") (pin "5") (pinfunction "R5_5") (pintype "passive"))
    )
    (net (code "68") (name "Net-(LED6-K)") (class "Default")
      (node (ref "LED6") (pin "2") (pinfunction "K_2") (pintype "passive"))
      (node (ref "R2") (pin "4") (pinfunction "R4_4") (pintype "passive"))
    )
    (net (code "69") (name "Net-(LED7-K)") (class "Default")
      (node (ref "LED7") (pin "2") (pinfunction "K_2") (pintype "passive"))
      (node (ref "R2") (pin "3") (pinfunction "R3_3") (pintype "passive"))
    )
    (net (code "70") (name "Net-(LED8-K)") (class "Default")
      (node (ref "LED8") (pin "2") (pinfunction "K_2") (pintype "passive"))
      (node (ref "R2") (pin "2") (pinfunction "R2_2") (pintype "passive"))
    )
    (net (code "71") (name "Net-(LED9-K)") (class "Default")
      (node (ref "LED9") (pin "2") (pinfunction "K_2") (pintype "passive"))
      (node (ref "R2") (pin "1") (pinfunction "R1_1") (pintype "passive"))
    )
    (net (code "72") (name "Net-(P6-CANH)") (class "Default")
      (node (ref "P6") (pin "6") (pinfunction "CANH_6") (pintype "passive"))
      (node (ref "P7") (pin "1") (pinfunction "1_1") (pintype "passive"))
      (node (ref "R14") (pin "2") (pinfunction "2_2") (pintype "passive"))
      (node (ref "R15") (pin "2") (pinfunction "2_2") (pintype "passive"))
    )
    (net (code "73") (name "Net-(P6-CANL)") (class "Default")
      (node (ref "P6") (pin "7") (pinfunction "CANL_7") (pintype "passive"))
      (node (ref "P7") (pin "2") (pinfunction "2_2") (pintype "passive"))
      (node (ref "R14") (pin "1") (pinfunction "1_1") (pintype "passive"))
      (node (ref "R15") (pin "1") (pinfunction "1_1") (pintype "passive"))
    )
    (net (code "74") (name "Net-(R2-COM)") (class "Default")
      (node (ref "P3") (pin "2") (pinfunction "2_2") (pintype "passive"))
      (node (ref "R2") (pin "0") (pinfunction "COM_0") (pintype "passive"))
    )
    (net (code "75") (name "Net-(U2B-VBAT)") (class "Default")
      (node (ref "B1") (pin "1") (pintype "passive"))
      (node (ref "U2") (pin "1") (pinfunction "VBAT_1") (pintype "power_in"))
    )
    (net (code "76") (name "Net-(U4-VCC)") (class "Default")
      (node (ref "P8") (pin "2") (pinfunction "2_2") (pintype "passive"))
      (node (ref "U4") (pin "1") (pinfunction "VCC_1") (pintype "passive"))
    )
    (net (code "77") (name "Net-(U6-D+)") (class "Default")
      (node (ref "U5") (pin "3") (pinfunction "0_3") (pintype "passive"))
      (node (ref "U6") (pin "3") (pinfunction "D+_3") (pintype "passive"))
    )
    (net (code "78") (name "Net-(U6-D-)") (class "Default")
      (node (ref "U5") (pin "1") (pinfunction "0_1") (pintype "passive"))
      (node (ref "U6") (pin "2") (pinfunction "D-_2") (pintype "passive"))
    )
    (net (code "79") (name "Net-(U6-VBUS)") (class "Default")
      (node (ref "S1") (pin "2") (pinfunction "2_2") (pintype "passive"))
      (node (ref "U6") (pin "1") (pinfunction "VBUS_1") (pintype "passive"))
    )
    (net (code "80") (name "unconnected-(LCD1-DB.0-Pad7)") (class "Default")
      (node (ref "LCD1") (pin "7") (pinfunction "DB.0_7") (pintype "passive"))
    )
    (net (code "81") (name "unconnected-(LCD1-DB.1-Pad8)") (class "Default")
      (node (ref "LCD1") (pin "8") (pinfunction "DB.1_8") (pintype "passive"))
    )
    (net (code "82") (name "unconnected-(LCD1-DB.2-Pad9)") (class "Default")
      (node (ref "LCD1") (pin "9") (pinfunction "DB.2_9") (pintype "passive"))
    )
    (net (code "83") (name "unconnected-(LCD1-DB.3-Pad10)") (class "Default")
      (node (ref "LCD1") (pin "10") (pinfunction "DB.3_10") (pintype "passive"))
    )
    (net (code "84") (name "unconnected-(M1-PadS)") (class "Default")
      (node (ref "M1") (pin "S") (pinfunction "S_S") (pintype "passive"))
    )
    (net (code "85") (name "unconnected-(M2-PadS)") (class "Default")
      (node (ref "M2") (pin "S") (pinfunction "S_S") (pintype "passive"))
    )
    (net (code "86") (name "unconnected-(M3-PadS)") (class "Default")
      (node (ref "M3") (pin "S") (pinfunction "S_S") (pintype "passive"))
    )
    (net (code "87") (name "unconnected-(M4-PadS)") (class "Default")
      (node (ref "M4") (pin "S") (pinfunction "S_S") (pintype "passive"))
    )
    (net (code "88") (name "unconnected-(P1-Pad3)") (class "Default")
      (node (ref "P1") (pin "3") (pinfunction "3_3") (pintype "passive"))
    )
    (net (code "89") (name "unconnected-(P6-Vref-Pad8)") (class "Default")
      (node (ref "P6") (pin "8") (pinfunction "Vref_8") (pintype "passive"))
    )
    (net (code "90") (name "unconnected-(U3-NC-Pad1)") (class "Default")
      (node (ref "U3") (pin "1") (pinfunction "NC_1") (pintype "passive"))
    )
    (net (code "91") (name "unconnected-(U3-NC-Pad2)") (class "Default")
      (node (ref "U3") (pin "2") (pinfunction "NC_2") (pintype "passive"))
    )
    (net (code "92") (name "unconnected-(U5-0-Pad2)") (class "Default")
      (node (ref "U5") (pin "2") (pinfunction "0_2") (pintype "passive"))
    )
    (net (code "93") (name "unconnected-(U6-ID-Pad4)") (class "Default")
      (node (ref "U6") (pin "4") (pinfunction "ID_4") (pintype "passive"))
    )
    (net (code "94") (name "unconnected-(VR1-CCW-Pad1)") (class "Default")
      (node (ref "VR1") (pin "1") (pinfunction "CCW_1") (pintype "passive"))
    )
  )
)
